# SCH__OldSensor.net
KiCad netlist of a schematic drawn in Altium Designer
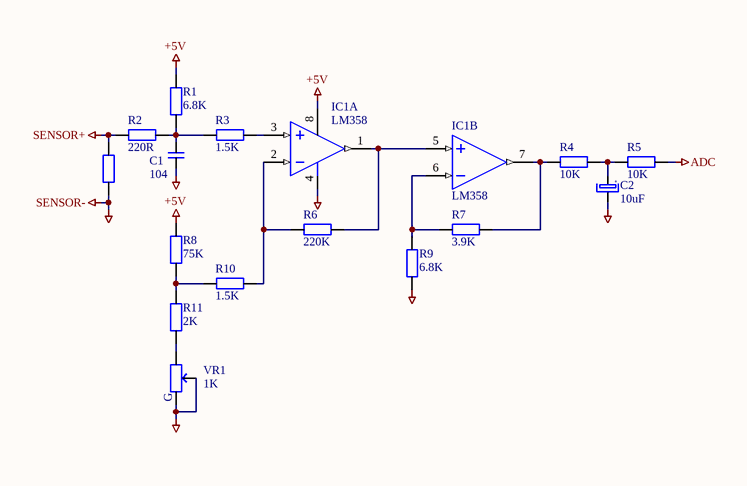
[diagram p0: [SCH]_OldSensor.SchDoc]

(export (version "E")
  (design (tool "Eeschema 10.0.6"))
  (components
    (comp (ref "C1")
      (value "104")
      (footprint "Cap-Non-150mil")
      (description "Non-polar capacitor")
      (libsource (lib "Library") (part "Cap-Non-Dip"))
    )
    (comp (ref "C2")
      (value "10uF")
      (footprint "Cap-P-1.5/4")
      (description "Polarized capacitor")
      (libsource (lib "Library") (part "Cap-Pol-Dip"))
    )
    (comp (ref "IC1")
      (value "LM358")
      (footprint "DIP8")
      (description "Low-Power Dual Operational Amplifier")
      (libsource (lib "Library") (part "LM358"))
    )
    (comp (ref "R1")
      (value "6.8K")
      (footprint "Res1/4W")
      (description "Resistor 1/4W")
      (libsource (lib "Library") (part "Res 1/4W"))
    )
    (comp (ref "R2")
      (value "220R")
      (footprint "Res1/4W")
      (description "Resistor 1/4W")
      (libsource (lib "Library") (part "Res 1/4W"))
    )
    (comp (ref "R3")
      (value "1.5K")
      (footprint "Res1/4W")
      (description "Resistor 1/4W")
      (libsource (lib "Library") (part "Res 1/4W"))
    )
    (comp (ref "R4")
      (value "10K")
      (footprint "Res1/4W")
      (description "Resistor 1/4W")
      (libsource (lib "Library") (part "Res 1/4W"))
    )
    (comp (ref "R5")
      (value "10K")
      (footprint "Res1/4W")
      (description "Resistor 1/4W")
      (libsource (lib "Library") (part "Res 1/4W"))
    )
    (comp (ref "R6")
      (value "220K")
      (footprint "Res1/4W")
      (description "Resistor 1/4W")
      (libsource (lib "Library") (part "Res 1/4W"))
    )
    (comp (ref "R7")
      (value "3.9K")
      (footprint "Res1/4W")
      (description "Resistor 1/4W")
      (libsource (lib "Library") (part "Res 1/4W"))
    )
    (comp (ref "R8")
      (value "75K")
      (footprint "Res1/4W")
      (description "Resistor 1/4W")
      (libsource (lib "Library") (part "Res 1/4W"))
    )
    (comp (ref "R9")
      (value "6.8K")
      (footprint "Res1/4W")
      (description "Resistor 1/4W")
      (libsource (lib "Library") (part "Res 1/4W"))
    )
    (comp (ref "R10")
      (value "1.5K")
      (footprint "Res1/4W")
      (description "Resistor 1/4W")
      (libsource (lib "Library") (part "Res 1/4W"))
    )
    (comp (ref "R11")
      (value "2K")
      (footprint "Res1/4W")
      (description "Resistor 1/4W")
      (libsource (lib "Library") (part "Res 1/4W"))
    )
    (comp (ref "SENSOR1")
      (value "5R")
      (footprint "Res1/4W")
      (description "Resistor 1/4W")
      (libsource (lib "Library") (part "Res 1/4W"))
    )
    (comp (ref "VR1")
      (value "1K")
      (footprint "VR-S3")
      (description "Variable Resistor")
      (libsource (lib "Library") (part "Res-Var-Singal"))
    )
  )
  (nets
    (net (code "1") (name "+5V") (class "Default")
      (node (ref "IC1") (pin "8") (pinfunction "+V_8") (pintype "passive"))
      (node (ref "R1") (pin "2") (pinfunction "2_2") (pintype "passive"))
      (node (ref "R8") (pin "2") (pinfunction "2_2") (pintype "passive"))
    )
    (net (code "2") (name "ADC") (class "Default")
      (node (ref "R5") (pin "2") (pinfunction "2_2") (pintype "passive"))
    )
    (net (code "3") (name "GND") (class "Default")
      (node (ref "C1") (pin "1") (pinfunction "1_1") (pintype "passive"))
      (node (ref "C2") (pin "2") (pinfunction "2_2") (pintype "passive"))
      (node (ref "IC1") (pin "4") (pinfunction "-V_4") (pintype "passive"))
      (node (ref "R9") (pin "1") (pinfunction "1_1") (pintype "passive"))
      (node (ref "SENSOR1") (pin "1") (pinfunction "1_1") (pintype "passive"))
      (node (ref "VR1") (pin "1") (pinfunction "1_1") (pintype "passive"))
      (node (ref "VR1") (pin "2") (pinfunction "2_2") (pintype "passive"))
    )
    (net (code "4") (name "Net-(C1-Pad2)") (class "Default")
      (node (ref "C1") (pin "2") (pinfunction "2_2") (pintype "passive"))
      (node (ref "R1") (pin "1") (pinfunction "1_1") (pintype "passive"))
      (node (ref "R2") (pin "2") (pinfunction "2_2") (pintype "passive"))
      (node (ref "R3") (pin "1") (pinfunction "1_1") (pintype "passive"))
    )
    (net (code "5") (name "Net-(C2-Pad1)") (class "Default")
      (node (ref "C2") (pin "1") (pinfunction "1_1") (pintype "passive"))
      (node (ref "R4") (pin "2") (pinfunction "2_2") (pintype "passive"))
      (node (ref "R5") (pin "1") (pinfunction "1_1") (pintype "passive"))
    )
    (net (code "6") (name "Net-(IC1A-IN+)") (class "Default")
      (node (ref "IC1") (pin "3") (pinfunction "IN+_3") (pintype "input"))
      (node (ref "R3") (pin "2") (pinfunction "2_2") (pintype "passive"))
    )
    (net (code "7") (name "Net-(IC1A-IN-)") (class "Default")
      (node (ref "IC1") (pin "2") (pinfunction "IN-_2") (pintype "input"))
      (node (ref "R10") (pin "2") (pinfunction "2_2") (pintype "passive"))
      (node (ref "R6") (pin "1") (pinfunction "1_1") (pintype "passive"))
    )
    (net (code "8") (name "Net-(IC1A-OUT)") (class "Default")
      (node (ref "IC1") (pin "1") (pinfunction "OUT_1") (pintype "output"))
      (node (ref "IC1") (pin "5") (pinfunction "IN+_5") (pintype "input"))
      (node (ref "R6") (pin "2") (pinfunction "2_2") (pintype "passive"))
    )
    (net (code "9") (name "Net-(IC1B-IN-)") (class "Default")
      (node (ref "IC1") (pin "6") (pinfunction "IN-_6") (pintype "input"))
      (node (ref "R7") (pin "1") (pinfunction "1_1") (pintype "passive"))
      (node (ref "R9") (pin "2") (pinfunction "2_2") (pintype "passive"))
    )
    (net (code "10") (name "Net-(IC1B-OUT)") (class "Default")
      (node (ref "IC1") (pin "7") (pinfunction "OUT_7") (pintype "output"))
      (node (ref "R4") (pin "1") (pinfunction "1_1") (pintype "passive"))
      (node (ref "R7") (pin "2") (pinfunction "2_2") (pintype "passive"))
    )
    (net (code "11") (name "Net-(R10-Pad1)") (class "Default")
      (node (ref "R10") (pin "1") (pinfunction "1_1") (pintype "passive"))
      (node (ref "R11") (pin "2") (pinfunction "2_2") (pintype "passive"))
      (node (ref "R8") (pin "1") (pinfunction "1_1") (pintype "passive"))
    )
    (net (code "12") (name "Net-(R11-Pad1)") (class "Default")
      (node (ref "R11") (pin "1") (pinfunction "1_1") (pintype "passive"))
      (node (ref "VR1") (pin "3") (pinfunction "3_3") (pintype "passive"))
    )
    (net (code "13") (name "SENSOR+") (class "Default")
      (node (ref "R2") (pin "1") (pinfunction "1_1") (pintype "passive"))
      (node (ref "SENSOR1") (pin "2") (pinfunction "2_2") (pintype "passive"))
    )
  )
)
